# Powering.net
KiCad netlist of a schematic drawn in Altium Designer
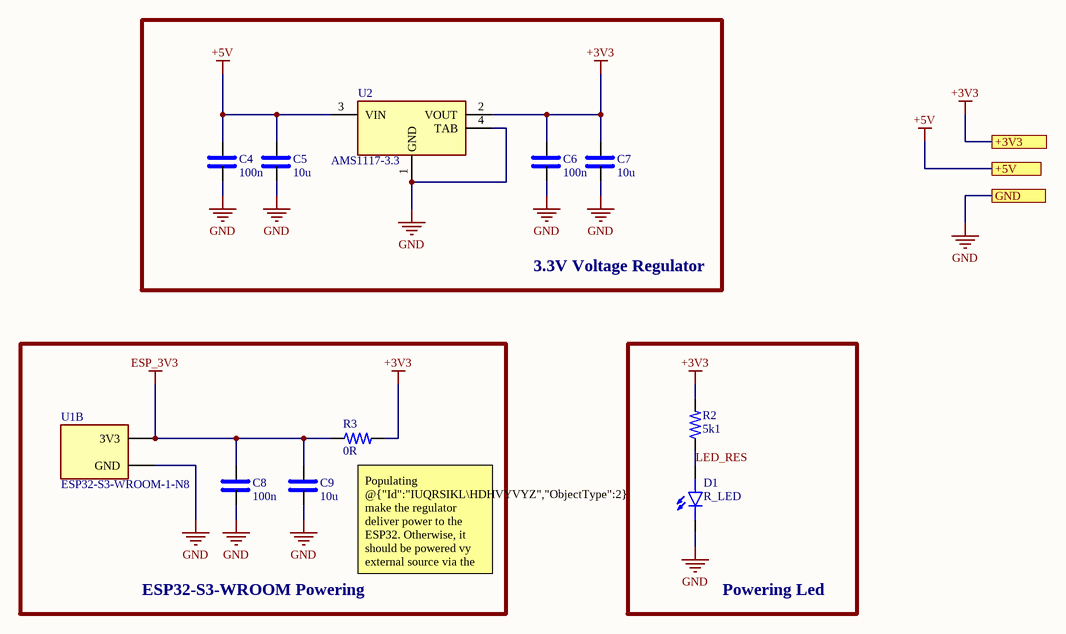
[diagram p0: Powering.SchDoc]

(export (version "E")
  (design (tool "Eeschema 10.0.6"))
  (components
    (comp (ref "C4")
      (value "100n")
      (footprint "0402 CAP")
      (description "Multilayer Ceramic Capacitor, 0.1 uF, 25 V, ï¿½ 10%, X7R, 0402 [1005 Metric]")
      (fields
        (field (name "MANUFACTURER") "Samsung")
        (field (name "MANUFACTURER PART NUMBER") "CL05B104KA5NNNC")
      )
      (libsource (lib "Integrated_Library") (part "0402 SMD Capacitor"))
    )
    (comp (ref "C5")
      (value "10u")
      (footprint "FP-GCJ188-0_2-IPC_C")
      (description "Multilayer Ceramic Capacitor, 10 uF, 25 V, ï¿½ 10%, X5R, 0603 [1608 Metric]")
      (fields
        (field (name "MANUFACTURER") "Murata")
        (field (name "MANUFACTURER PART NUMBER") "GRM188R61E106KA73D")
      )
      (libsource (lib "Integrated_Library") (part "0603 SMD CAP"))
    )
    (comp (ref "C6")
      (value "100n")
      (footprint "0402 CAP")
      (description "Multilayer Ceramic Capacitor, 0.1 uF, 25 V, ï¿½ 10%, X7R, 0402 [1005 Metric]")
      (fields
        (field (name "MANUFACTURER") "Samsung")
        (field (name "MANUFACTURER PART NUMBER") "CL05B104KA5NNNC")
      )
      (libsource (lib "Integrated_Library") (part "0402 SMD Capacitor"))
    )
    (comp (ref "C7")
      (value "10u")
      (footprint "FP-GCJ188-0_2-IPC_C")
      (description "Multilayer Ceramic Capacitor, 10 uF, 25 V, ï¿½ 10%, X5R, 0603 [1608 Metric]")
      (fields
        (field (name "MANUFACTURER") "Murata")
        (field (name "MANUFACTURER PART NUMBER") "GRM188R61E106KA73D")
      )
      (libsource (lib "Integrated_Library") (part "0603 SMD CAP"))
    )
    (comp (ref "C8")
      (value "100n")
      (footprint "0402 CAP")
      (description "Multilayer Ceramic Capacitor, 0.1 uF, 25 V, ï¿½ 10%, X7R, 0402 [1005 Metric]")
      (fields
        (field (name "MANUFACTURER") "Samsung")
        (field (name "MANUFACTURER PART NUMBER") "CL05B104KA5NNNC")
      )
      (libsource (lib "Integrated_Library") (part "0402 SMD Capacitor"))
    )
    (comp (ref "C9")
      (value "10u")
      (footprint "FP-GCJ188-0_2-IPC_C")
      (description "Multilayer Ceramic Capacitor, 10 uF, 25 V, ï¿½ 10%, X5R, 0603 [1608 Metric]")
      (fields
        (field (name "MANUFACTURER") "Murata")
        (field (name "MANUFACTURER PART NUMBER") "GRM188R61E106KA73D")
      )
      (libsource (lib "Integrated_Library") (part "0603 SMD CAP"))
    )
    (comp (ref "D1")
      (value "R_LED")
      (footprint "LEDC2012X70N")
      (description "LED Uni-Color Red 2-Pin Chip 0805 T/R")
      (fields (field (name "MP") "597-3305-607F"))
      (libsource (lib "Integrated_Library") (part "597-3305-607F"))
    )
    (comp (ref "R2")
      (value "5k1")
      (footprint "0402 RES")
      (description "General Purpose Chip Resistor Thick Film 0402 5.1kOhm 1% Paper T/R")
      (fields
        (field (name "MANUFACTURER") "Yageo")
        (field (name "MANUFACTURER PART NUMBER") "RC0402FR-7W5K1L")
      )
      (libsource (lib "Integrated_Library") (part "0402 SMD Resistor"))
    )
    (comp (ref "R3")
      (value "0R")
      (footprint "0402 RES")
      (description "SMD Chip Resistor, Jumper, 0 ohm, 100 mW, 0402 [1005 Metric], Thick Film, General Purpose")
      (fields
        (field (name "MANUFACTURER") "Panasonic")
        (field (name "MANUFACTURER PART NUMBER") "ERJ-2GE0R00X")
      )
      (libsource (lib "Integrated_Library") (part "0402 SMD Resistor"))
    )
    (comp (ref "U1")
      (value "ESP32-S3-WROOM-1-N8")
      (footprint "XCVR_ESP32-S3-WROOM-1-N8")
      (fields (field (name "MF") "{'manufacturer': u'Espressif Systems'}"))
      (libsource (lib "Integrated_Library") (part "ESP32-S3-WROOM-1-N8"))
    )
    (comp (ref "U2")
      (value "AMS1117-3.3")
      (footprint "SOT229P700X180-4N")
      (description "Sot223/Pkg 1-Amp 3.3-Volt Low Drop Out Voltage Regulatator")
      (fields (field (name "MF") "Advanced Monolithic Systems"))
      (libsource (lib "Integrated_Library") (part "AMS1117-3.3"))
    )
  )
  (nets
    (net (code "1") (name "+3V3") (class "Default")
      (node (ref "C6") (pin "2") (pinfunction "2_2") (pintype "passive"))
      (node (ref "C7") (pin "2") (pinfunction "2_2") (pintype "passive"))
      (node (ref "R2") (pin "2") (pinfunction "2_2") (pintype "passive"))
      (node (ref "R3") (pin "2") (pinfunction "2_2") (pintype "passive"))
      (node (ref "U2") (pin "2") (pinfunction "VOUT_2") (pintype "power_in"))
    )
    (net (code "2") (name "+5V") (class "Default")
      (node (ref "C4") (pin "2") (pinfunction "2_2") (pintype "passive"))
      (node (ref "C5") (pin "2") (pinfunction "2_2") (pintype "passive"))
      (node (ref "U2") (pin "3") (pinfunction "VIN_3") (pintype "power_in"))
    )
    (net (code "3") (name "/LED_RES") (class "Default")
      (node (ref "D1") (pin "A") (pinfunction "A_A") (pintype "passive"))
      (node (ref "R2") (pin "1") (pinfunction "1_1") (pintype "passive"))
    )
    (net (code "4") (name "ESP_3V3") (class "Default")
      (node (ref "C8") (pin "2") (pinfunction "2_2") (pintype "passive"))
      (node (ref "C9") (pin "2") (pinfunction "2_2") (pintype "passive"))
      (node (ref "R3") (pin "1") (pinfunction "1_1") (pintype "passive"))
      (node (ref "U1") (pin "2") (pinfunction "3V3_2") (pintype "power_in"))
    )
    (net (code "5") (name "GND") (class "Default")
      (node (ref "C4") (pin "1") (pinfunction "1_1") (pintype "passive"))
      (node (ref "C5") (pin "1") (pinfunction "1_1") (pintype "passive"))
      (node (ref "C6") (pin "1") (pinfunction "1_1") (pintype "passive"))
      (node (ref "C7") (pin "1") (pinfunction "1_1") (pintype "passive"))
      (node (ref "C8") (pin "1") (pinfunction "1_1") (pintype "passive"))
      (node (ref "C9") (pin "1") (pinfunction "1_1") (pintype "passive"))
      (node (ref "D1") (pin "C") (pinfunction "C_C") (pintype "passive"))
      (node (ref "U1") (pin "1") (pinfunction "GND_1") (pintype "power_in"))
      (node (ref "U2") (pin "1") (pinfunction "GND_1") (pintype "power_in"))
      (node (ref "U2") (pin "4") (pinfunction "TAB_4") (pintype "passive"))
    )
  )
)
